# 1stschem.net
KiCad netlist of a schematic drawn in EAGLE
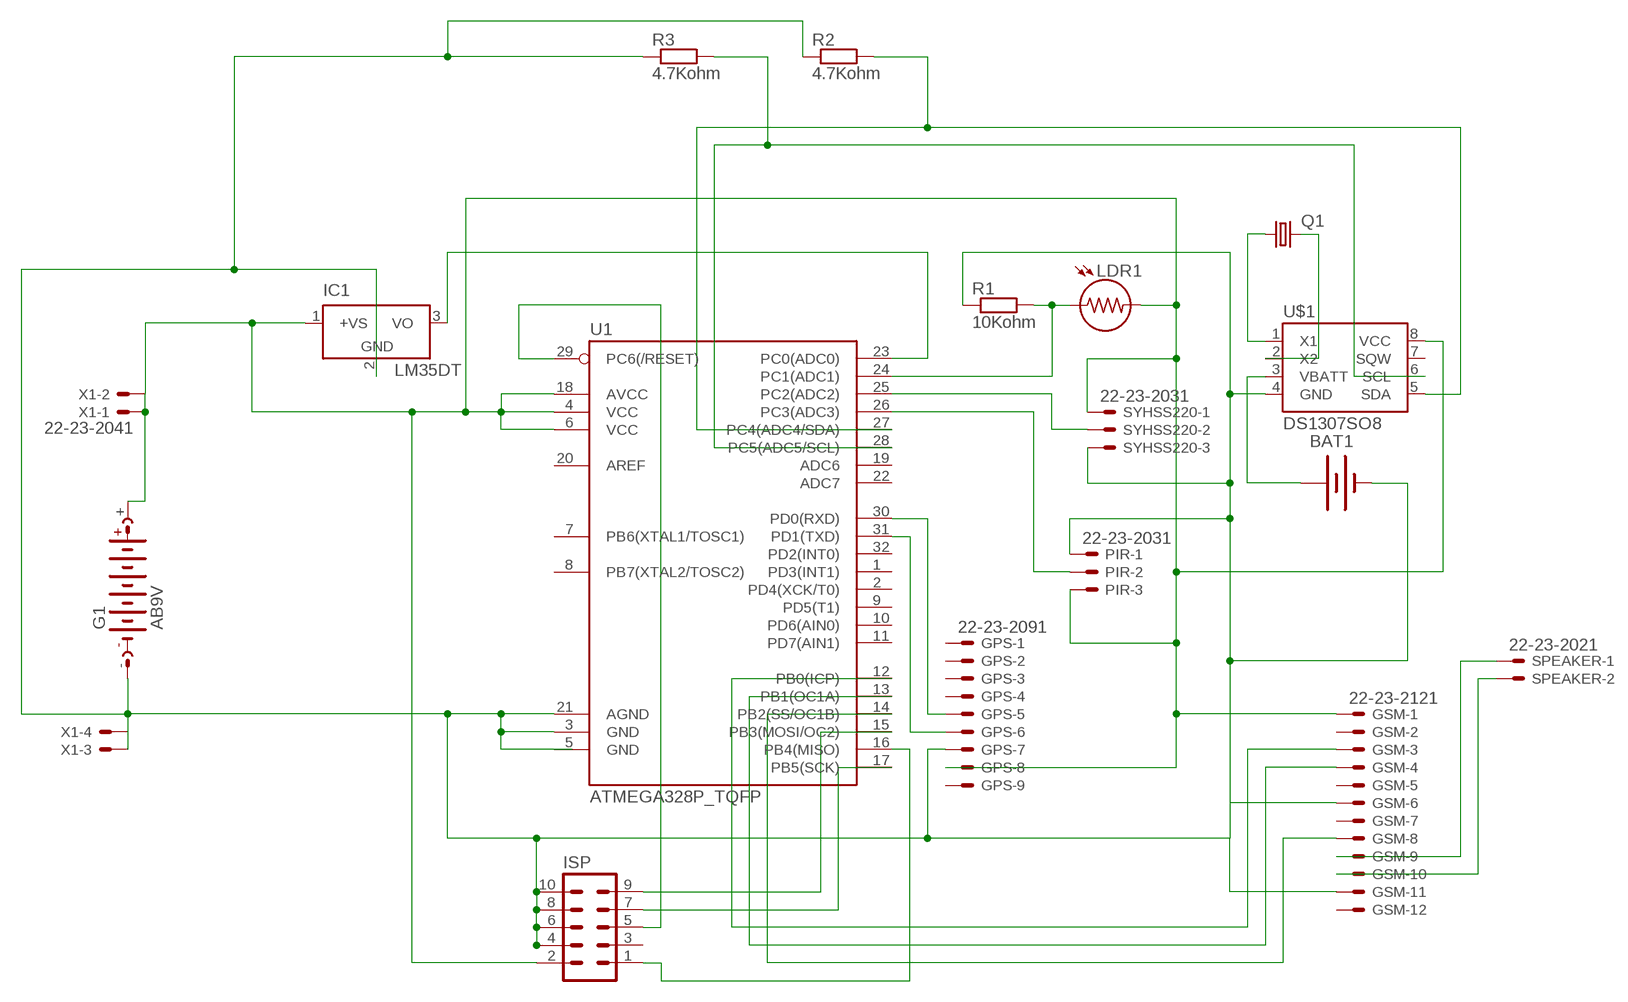
[diagram p0: schematic, sheet 1]

(export (version "E")
  (design (tool "Eeschema 10.0.6"))
  (components
    (comp (ref "BAT1")
      (value "BATTERY20PTH")
      (footprint "eagle-import:BATTCOM_20MM_PTH")
      (libsource (lib "eagle-import") (part "BATTERY20PTH"))
    )
    (comp (ref "G1")
      (value "AB9V")
      (footprint "eagle-import:AB9V")
      (libsource (lib "eagle-import") (part "AB9V"))
    )
    (comp (ref "GPS")
      (value "22-23-2091")
      (footprint "eagle-import:22-23-2091")
      (fields (field (name "MF") "MOLEX"))
      (libsource (lib "eagle-import") (part "22-23-2091"))
    )
    (comp (ref "GSM")
      (value "22-23-2121")
      (footprint "eagle-import:22-23-2121")
      (fields (field (name "MF") "MOLEX"))
      (libsource (lib "eagle-import") (part "22-23-2121"))
    )
    (comp (ref "IC1")
      (value "LM35DT")
      (footprint "eagle-import:TO220V")
      (libsource (lib "eagle-import") (part "LM35DT"))
    )
    (comp (ref "ISP")
      (value "ML10")
      (footprint "eagle-import:ML10")
      (libsource (lib "eagle-import") (part "ML10"))
    )
    (comp (ref "LDR1")
      (value "LDR5MM")
      (footprint "eagle-import:LDR338-54C")
      (libsource (lib "eagle-import") (part "LDR5MM"))
    )
    (comp (ref "PIR")
      (value "22-23-2031")
      (footprint "eagle-import:22-23-2031")
      (fields (field (name "MF") "MOLEX"))
      (libsource (lib "eagle-import") (part "22-23-2031"))
    )
    (comp (ref "Q1")
      (value "CRYSTALTC26H")
      (footprint "eagle-import:TC26H")
      (libsource (lib "eagle-import") (part "CRYSTALTC26H"))
    )
    (comp (ref "R1")
      (value "10Kohm")
      (footprint "eagle-import:R0207_4")
      (libsource (lib "eagle-import") (part "6MM-EU4"))
    )
    (comp (ref "R2")
      (value "4.7Kohm")
      (footprint "eagle-import:R0207_4")
      (libsource (lib "eagle-import") (part "6MM-EU4"))
    )
    (comp (ref "R3")
      (value "4.7Kohm")
      (footprint "eagle-import:R0207_4")
      (libsource (lib "eagle-import") (part "6MM-EU4"))
    )
    (comp (ref "SPEAKER")
      (value "22-23-2021")
      (footprint "eagle-import:22-23-2021")
      (fields (field (name "MF") "MOLEX"))
      (libsource (lib "eagle-import") (part "22-23-2021"))
    )
    (comp (ref "SYHSS220")
      (value "22-23-2031")
      (footprint "eagle-import:22-23-2031")
      (fields (field (name "MF") "MOLEX"))
      (libsource (lib "eagle-import") (part "22-23-2031"))
    )
    (comp (ref "U$1")
      (value "DS1307SO8")
      (footprint "eagle-import:SO08")
      (libsource (lib "eagle-import") (part "DS1307SO8"))
    )
    (comp (ref "U1")
      (value "ATMEGA328P_TQFP")
      (footprint "eagle-import:TQFP32-08")
      (libsource (lib "eagle-import") (part "ATMEGA328P_TQFP"))
    )
    (comp (ref "X1")
      (value "22-23-2041")
      (footprint "eagle-import:22-23-2041")
      (fields (field (name "MF") "MOLEX"))
      (libsource (lib "eagle-import") (part "22-23-2041"))
    )
  )
  (nets
    (net (code "1") (name "Net-(BAT1-+)") (class "Default")
      (node (ref "BAT1") (pin "1") (pinfunction "+_1") (pintype "power_in"))
      (node (ref "U$1") (pin "3") (pinfunction "VBATT_3") (pintype "bidirectional"))
    )
    (net (code "2") (name "Net-(BAT1--)") (class "Default")
      (node (ref "BAT1") (pin "2") (pinfunction "-_2") (pintype "power_in"))
      (node (ref "G1") (pin "-") (pinfunction "-_-") (pintype "passive"))
      (node (ref "GPS") (pin "7") (pinfunction "S_7") (pintype "passive"))
      (node (ref "GSM") (pin "11") (pinfunction "S_11") (pintype "passive"))
      (node (ref "GSM") (pin "6") (pinfunction "S_6") (pintype "passive"))
      (node (ref "IC1") (pin "2") (pinfunction "GND_2") (pintype "power_in"))
      (node (ref "ISP") (pin "10") (pinfunction "10_10") (pintype "passive"))
      (node (ref "ISP") (pin "4") (pinfunction "4_4") (pintype "passive"))
      (node (ref "ISP") (pin "6") (pinfunction "6_6") (pintype "passive"))
      (node (ref "ISP") (pin "8") (pinfunction "8_8") (pintype "passive"))
      (node (ref "PIR") (pin "1") (pinfunction "S_1") (pintype "passive"))
      (node (ref "R1") (pin "1") (pinfunction "1_1") (pintype "passive"))
      (node (ref "R2") (pin "1") (pinfunction "1_1") (pintype "passive"))
      (node (ref "R3") (pin "1") (pinfunction "1_1") (pintype "passive"))
      (node (ref "SYHSS220") (pin "3") (pinfunction "S_3") (pintype "passive"))
      (node (ref "U$1") (pin "4") (pinfunction "GND_4") (pintype "bidirectional"))
      (node (ref "U1") (pin "21") (pinfunction "AGND_21") (pintype "bidirectional"))
      (node (ref "U1") (pin "3") (pinfunction "GND_3") (pintype "bidirectional"))
      (node (ref "X1") (pin "3") (pinfunction "S_3") (pintype "passive"))
      (node (ref "X1") (pin "4") (pinfunction "S_4") (pintype "passive"))
    )
    (net (code "3") (name "Net-(GPSE-S)") (class "Default")
      (node (ref "GPS") (pin "5") (pinfunction "S_5") (pintype "passive"))
      (node (ref "U1") (pin "30") (pinfunction "PD0(RXD)_30") (pintype "bidirectional"))
    )
    (net (code "4") (name "Net-(GPSF-S)") (class "Default")
      (node (ref "GPS") (pin "6") (pinfunction "S_6") (pintype "passive"))
      (node (ref "U1") (pin "31") (pinfunction "PD1(TXD)_31") (pintype "bidirectional"))
    )
    (net (code "5") (name "Net-(GPSH-S)") (class "Default")
      (node (ref "G1") (pin "+") (pinfunction "+_+") (pintype "passive"))
      (node (ref "GPS") (pin "8") (pinfunction "S_8") (pintype "passive"))
      (node (ref "GSM") (pin "1") (pinfunction "S_1") (pintype "passive"))
      (node (ref "IC1") (pin "1") (pinfunction "+VS_1") (pintype "input"))
      (node (ref "ISP") (pin "2") (pinfunction "2_2") (pintype "passive"))
      (node (ref "LDR1") (pin "2") (pinfunction "2_2") (pintype "passive"))
      (node (ref "PIR") (pin "3") (pinfunction "S_3") (pintype "passive"))
      (node (ref "SYHSS220") (pin "1") (pinfunction "S_1") (pintype "passive"))
      (node (ref "U$1") (pin "8") (pinfunction "VCC_8") (pintype "bidirectional"))
      (node (ref "U1") (pin "18") (pinfunction "AVCC_18") (pintype "bidirectional"))
      (node (ref "U1") (pin "4") (pinfunction "VCC_4") (pintype "bidirectional"))
      (node (ref "U1") (pin "6") (pinfunction "VCC_6") (pintype "bidirectional"))
      (node (ref "X1") (pin "1") (pinfunction "S_1") (pintype "passive"))
      (node (ref "X1") (pin "2") (pinfunction "S_2") (pintype "passive"))
    )
    (net (code "6") (name "Net-(GSMB-S)") (class "Default")
      (node (ref "GSM") (pin "10") (pinfunction "S_10") (pintype "passive"))
      (node (ref "SPEAKER") (pin "2") (pinfunction "S_2") (pintype "passive"))
    )
    (net (code "7") (name "Net-(GSMF-S)") (class "Default")
      (node (ref "GSM") (pin "3") (pinfunction "S_3") (pintype "passive"))
      (node (ref "U1") (pin "12") (pinfunction "PB0(ICP)_12") (pintype "bidirectional"))
    )
    (net (code "8") (name "Net-(GSMG-S)") (class "Default")
      (node (ref "GSM") (pin "4") (pinfunction "S_4") (pintype "passive"))
      (node (ref "U1") (pin "13") (pinfunction "PB1(OC1A)_13") (pintype "bidirectional"))
    )
    (net (code "9") (name "Net-(GSMK-S)") (class "Default")
      (node (ref "GSM") (pin "8") (pinfunction "S_8") (pintype "passive"))
      (node (ref "U1") (pin "14") (pinfunction "PB2(SS/OC1B)_14") (pintype "bidirectional"))
    )
    (net (code "10") (name "Net-(GSML-S)") (class "Default")
      (node (ref "GSM") (pin "9") (pinfunction "S_9") (pintype "passive"))
      (node (ref "SPEAKER") (pin "1") (pinfunction "S_1") (pintype "passive"))
    )
    (net (code "11") (name "Net-(IC1-VO)") (class "Default")
      (node (ref "IC1") (pin "3") (pinfunction "VO_3") (pintype "input"))
      (node (ref "U1") (pin "23") (pinfunction "PC0(ADC0)_23") (pintype "bidirectional"))
    )
    (net (code "12") (name "Net-(PIRB-S)") (class "Default")
      (node (ref "PIR") (pin "2") (pinfunction "S_2") (pintype "passive"))
      (node (ref "U1") (pin "26") (pinfunction "PC3(ADC3)_26") (pintype "bidirectional"))
    )
    (net (code "13") (name "Net-(SYHSS220B-S)") (class "Default")
      (node (ref "SYHSS220") (pin "2") (pinfunction "S_2") (pintype "passive"))
      (node (ref "U1") (pin "25") (pinfunction "PC2(ADC2)_25") (pintype "bidirectional"))
    )
    (net (code "14") (name "Net-(U$1-SCL)") (class "Default")
      (node (ref "R3") (pin "2") (pinfunction "2_2") (pintype "passive"))
      (node (ref "U$1") (pin "6") (pinfunction "SCL_6") (pintype "bidirectional"))
      (node (ref "U1") (pin "28") (pinfunction "PC5(ADC5/SCL)_28") (pintype "bidirectional"))
    )
    (net (code "15") (name "Net-(U$1-SDA)") (class "Default")
      (node (ref "R2") (pin "2") (pinfunction "2_2") (pintype "passive"))
      (node (ref "U$1") (pin "5") (pinfunction "SDA_5") (pintype "bidirectional"))
      (node (ref "U1") (pin "27") (pinfunction "PC4(ADC4/SDA)_27") (pintype "bidirectional"))
    )
    (net (code "16") (name "Net-(U$1-X1)") (class "Default")
      (node (ref "Q1") (pin "1") (pinfunction "1_1") (pintype "passive"))
      (node (ref "U$1") (pin "1") (pinfunction "X1_1") (pintype "bidirectional"))
    )
    (net (code "17") (name "Net-(U$1-X2)") (class "Default")
      (node (ref "Q1") (pin "2") (pinfunction "2_2") (pintype "passive"))
      (node (ref "U$1") (pin "2") (pinfunction "X2_2") (pintype "bidirectional"))
    )
    (net (code "18") (name "Net-(U1-PB3(MOSI{slash}OC2))") (class "Default")
      (node (ref "ISP") (pin "9") (pinfunction "9_9") (pintype "passive"))
      (node (ref "U1") (pin "15") (pinfunction "PB3(MOSI/OC2)_15") (pintype "bidirectional"))
    )
    (net (code "19") (name "Net-(U1-PB4(MISO))") (class "Default")
      (node (ref "ISP") (pin "1") (pinfunction "1_1") (pintype "passive"))
      (node (ref "U1") (pin "16") (pinfunction "PB4(MISO)_16") (pintype "bidirectional"))
    )
    (net (code "20") (name "Net-(U1-PB5(SCK))") (class "Default")
      (node (ref "ISP") (pin "7") (pinfunction "7_7") (pintype "passive"))
      (node (ref "U1") (pin "17") (pinfunction "PB5(SCK)_17") (pintype "bidirectional"))
    )
    (net (code "21") (name "Net-(U1-PC1(ADC1))") (class "Default")
      (node (ref "LDR1") (pin "1") (pinfunction "1_1") (pintype "passive"))
      (node (ref "R1") (pin "2") (pinfunction "2_2") (pintype "passive"))
      (node (ref "U1") (pin "24") (pinfunction "PC1(ADC1)_24") (pintype "bidirectional"))
    )
    (net (code "22") (name "Net-(U1-PC6({slash}RESET))") (class "Default")
      (node (ref "ISP") (pin "5") (pinfunction "5_5") (pintype "passive"))
      (node (ref "U1") (pin "29") (pinfunction "PC6(/RESET)_29") (pintype "bidirectional"))
    )
    (net (code "23") (name "unconnected-(GPSA-S-Pad1)") (class "Default")
      (node (ref "GPS") (pin "1") (pinfunction "S_1") (pintype "passive"))
    )
    (net (code "24") (name "unconnected-(GPSB-S-Pad2)") (class "Default")
      (node (ref "GPS") (pin "2") (pinfunction "S_2") (pintype "passive"))
    )
    (net (code "25") (name "unconnected-(GPSC-S-Pad3)") (class "Default")
      (node (ref "GPS") (pin "3") (pinfunction "S_3") (pintype "passive"))
    )
    (net (code "26") (name "unconnected-(GPSD-S-Pad4)") (class "Default")
      (node (ref "GPS") (pin "4") (pinfunction "S_4") (pintype "passive"))
    )
    (net (code "27") (name "unconnected-(GPSI-S-Pad9)") (class "Default")
      (node (ref "GPS") (pin "9") (pinfunction "S_9") (pintype "passive"))
    )
    (net (code "28") (name "unconnected-(GSMD-S-Pad12)") (class "Default")
      (node (ref "GSM") (pin "12") (pinfunction "S_12") (pintype "passive"))
    )
    (net (code "29") (name "unconnected-(GSME-S-Pad2)") (class "Default")
      (node (ref "GSM") (pin "2") (pinfunction "S_2") (pintype "passive"))
    )
    (net (code "30") (name "unconnected-(GSMH-S-Pad5)") (class "Default")
      (node (ref "GSM") (pin "5") (pinfunction "S_5") (pintype "passive"))
    )
    (net (code "31") (name "unconnected-(GSMJ-S-Pad7)") (class "Default")
      (node (ref "GSM") (pin "7") (pinfunction "S_7") (pintype "passive"))
    )
    (net (code "32") (name "unconnected-(ISP-Pad3)") (class "Default")
      (node (ref "ISP") (pin "3") (pinfunction "3_3") (pintype "passive"))
    )
    (net (code "33") (name "unconnected-(U$1-SQW-Pad7)") (class "Default")
      (node (ref "U$1") (pin "7") (pinfunction "SQW_7") (pintype "bidirectional"))
    )
    (net (code "34") (name "unconnected-(U1-ADC6-Pad19)") (class "Default")
      (node (ref "U1") (pin "19") (pinfunction "ADC6_19") (pintype "bidirectional"))
    )
    (net (code "35") (name "unconnected-(U1-ADC7-Pad22)") (class "Default")
      (node (ref "U1") (pin "22") (pinfunction "ADC7_22") (pintype "bidirectional"))
    )
    (net (code "36") (name "unconnected-(U1-AREF-Pad20)") (class "Default")
      (node (ref "U1") (pin "20") (pinfunction "AREF_20") (pintype "bidirectional"))
    )
    (net (code "37") (name "unconnected-(U1-GND-Pad5)") (class "Default")
      (node (ref "U1") (pin "5") (pinfunction "GND_5") (pintype "bidirectional"))
    )
    (net (code "38") (name "unconnected-(U1-PB6(XTAL1{slash}TOSC1)-Pad7)") (class "Default")
      (node (ref "U1") (pin "7") (pinfunction "PB6(XTAL1/TOSC1)_7") (pintype "bidirectional"))
    )
    (net (code "39") (name "unconnected-(U1-PB7(XTAL2{slash}TOSC2)-Pad8)") (class "Default")
      (node (ref "U1") (pin "8") (pinfunction "PB7(XTAL2/TOSC2)_8") (pintype "bidirectional"))
    )
    (net (code "40") (name "unconnected-(U1-PD2(INT0)-Pad32)") (class "Default")
      (node (ref "U1") (pin "32") (pinfunction "PD2(INT0)_32") (pintype "bidirectional"))
    )
    (net (code "41") (name "unconnected-(U1-PD3(INT1)-Pad1)") (class "Default")
      (node (ref "U1") (pin "1") (pinfunction "PD3(INT1)_1") (pintype "bidirectional"))
    )
    (net (code "42") (name "unconnected-(U1-PD4(XCK{slash}T0)-Pad2)") (class "Default")
      (node (ref "U1") (pin "2") (pinfunction "PD4(XCK/T0)_2") (pintype "bidirectional"))
    )
    (net (code "43") (name "unconnected-(U1-PD5(T1)-Pad9)") (class "Default")
      (node (ref "U1") (pin "9") (pinfunction "PD5(T1)_9") (pintype "bidirectional"))
    )
    (net (code "44") (name "unconnected-(U1-PD6(AIN0)-Pad10)") (class "Default")
      (node (ref "U1") (pin "10") (pinfunction "PD6(AIN0)_10") (pintype "bidirectional"))
    )
    (net (code "45") (name "unconnected-(U1-PD7(AIN1)-Pad11)") (class "Default")
      (node (ref "U1") (pin "11") (pinfunction "PD7(AIN1)_11") (pintype "bidirectional"))
    )
  )
)
